# Lab5.net
KiCad netlist of a schematic drawn in EAGLE
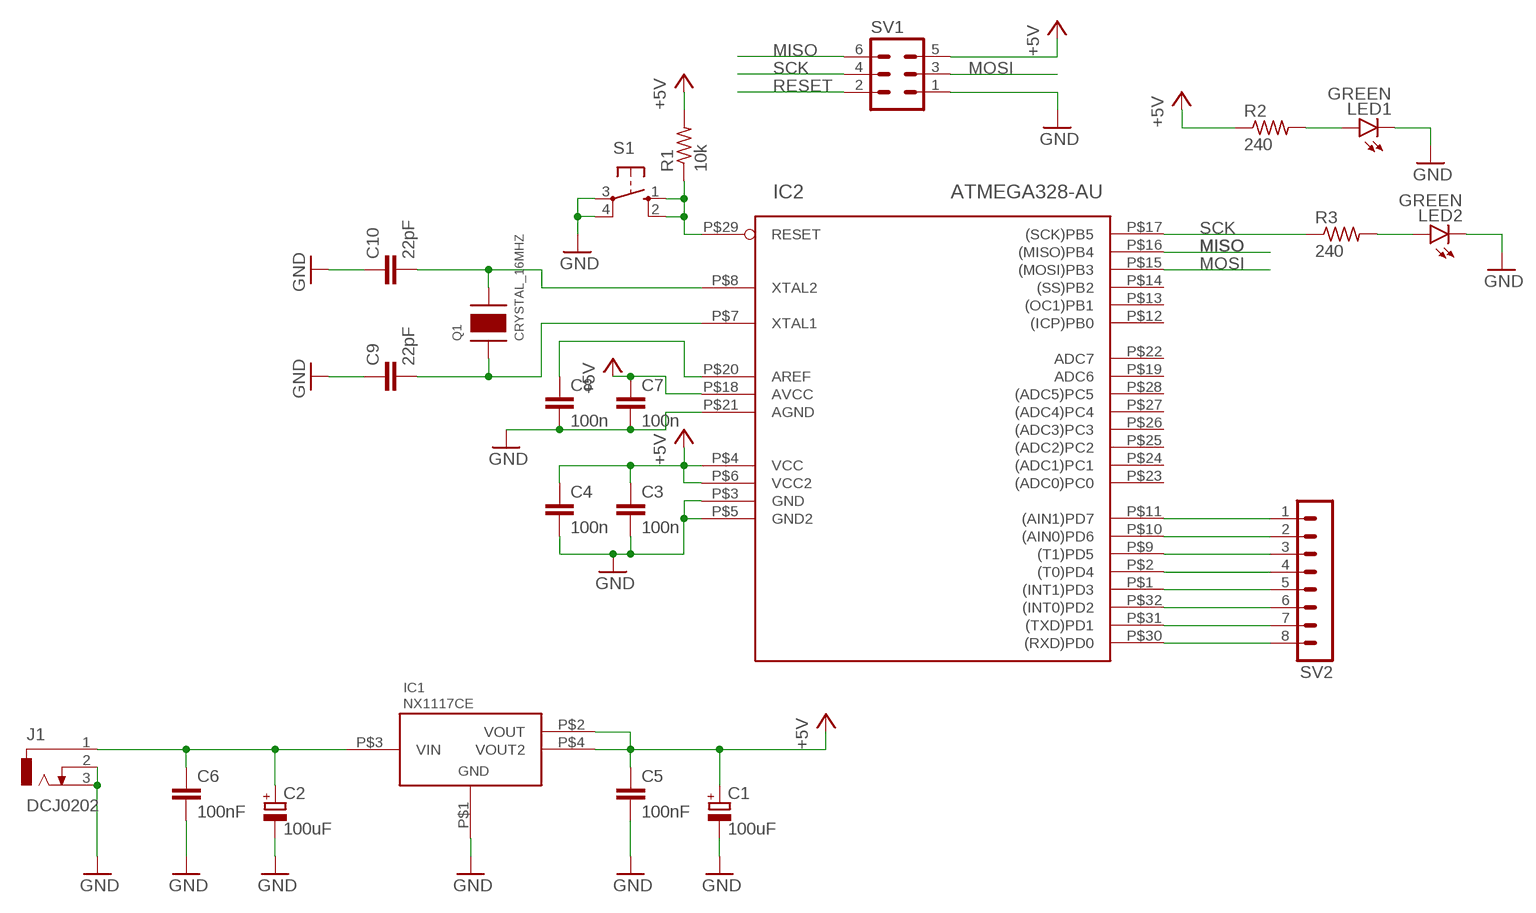
[diagram p0: schematic, sheet 1]

(export (version "E")
  (design (tool "Eeschema 10.0.6"))
  (components
    (comp (ref "C1")
      (value "100uF")
      (footprint "eagle-import:PANASONIC_D")
      (libsource (lib "eagle-import") (part "CPOL-EUD"))
    )
    (comp (ref "C2")
      (value "100uF")
      (footprint "eagle-import:PANASONIC_D")
      (libsource (lib "eagle-import") (part "CPOL-EUD"))
    )
    (comp (ref "C3")
      (value "100n")
      (footprint "eagle-import:C0603")
      (libsource (lib "eagle-import") (part "C-EUC0603"))
    )
    (comp (ref "C4")
      (value "100n")
      (footprint "eagle-import:C0603")
      (libsource (lib "eagle-import") (part "C-EUC0603"))
    )
    (comp (ref "C5")
      (value "100nF")
      (footprint "eagle-import:C0805")
      (libsource (lib "eagle-import") (part "C-EUC0805"))
    )
    (comp (ref "C6")
      (value "100nF")
      (footprint "eagle-import:C0805")
      (libsource (lib "eagle-import") (part "C-EUC0805"))
    )
    (comp (ref "C7")
      (value "100n")
      (footprint "eagle-import:C0603")
      (libsource (lib "eagle-import") (part "C-EUC0603"))
    )
    (comp (ref "C8")
      (value "100n")
      (footprint "eagle-import:C0603")
      (libsource (lib "eagle-import") (part "C-EUC0603"))
    )
    (comp (ref "C9")
      (value "22pF")
      (footprint "eagle-import:C0603")
      (libsource (lib "eagle-import") (part "C-EUC0603"))
    )
    (comp (ref "C10")
      (value "22pF")
      (footprint "eagle-import:C0603")
      (libsource (lib "eagle-import") (part "C-EUC0603"))
    )
    (comp (ref "IC1")
      (value "NX1117CE")
      (footprint "eagle-import:SOT223_NX")
      (libsource (lib "eagle-import") (part "NX1117CE"))
    )
    (comp (ref "IC2")
      (value "ATMEGA328-AU")
      (footprint "eagle-import:32-TQFP")
      (libsource (lib "eagle-import") (part "ATMEGA328-AU"))
    )
    (comp (ref "J1")
      (value "DCJ0202")
      (footprint "eagle-import:DCJ0202")
      (libsource (lib "eagle-import") (part "DCJ0202"))
    )
    (comp (ref "LED1")
      (value "GREEN")
      (footprint "eagle-import:CHIP-LED0603")
      (libsource (lib "eagle-import") (part "LEDCHIP-LED0603"))
    )
    (comp (ref "LED2")
      (value "GREEN")
      (footprint "eagle-import:CHIP-LED0603")
      (libsource (lib "eagle-import") (part "LEDCHIP-LED0603"))
    )
    (comp (ref "Q1")
      (value "CRYSTAL_16MHZ")
      (footprint "eagle-import:CRYSTAL_16MHZ")
      (libsource (lib "eagle-import") (part "CRYSTAL_16MHZ"))
    )
    (comp (ref "R1")
      (value "10k")
      (footprint "eagle-import:R0603")
      (libsource (lib "eagle-import") (part "R-US_R0603"))
    )
    (comp (ref "R2")
      (value "240")
      (footprint "eagle-import:R0603")
      (libsource (lib "eagle-import") (part "R-US_R0603"))
    )
    (comp (ref "R3")
      (value "240")
      (footprint "eagle-import:R0603")
      (libsource (lib "eagle-import") (part "R-US_R0603"))
    )
    (comp (ref "S1")
      (value "10-XX")
      (footprint "eagle-import:B3F-10XX")
      (fields (field (name "MPN") "B3F-1000"))
      (libsource (lib "eagle-import") (part "10-XX"))
    )
    (comp (ref "SV1")
      (value "MA03-2")
      (footprint "eagle-import:MA03-2")
      (libsource (lib "eagle-import") (part "MA03-2"))
    )
    (comp (ref "SV2")
      (value "MA08-1")
      (footprint "eagle-import:MA08-1")
      (libsource (lib "eagle-import") (part "MA08-1"))
    )
  )
  (nets
    (net (code "1") (name "+5V") (class "Default")
      (node (ref "C1") (pin "+") (pinfunction "+_+") (pintype "passive"))
      (node (ref "C3") (pin "1") (pinfunction "1_1") (pintype "passive"))
      (node (ref "C4") (pin "1") (pinfunction "1_1") (pintype "passive"))
      (node (ref "C5") (pin "1") (pinfunction "1_1") (pintype "passive"))
      (node (ref "C7") (pin "1") (pinfunction "1_1") (pintype "passive"))
      (node (ref "IC1") (pin "P$2") (pinfunction "VOUT_P$2") (pintype "bidirectional"))
      (node (ref "IC1") (pin "P$4") (pinfunction "VOUT2_P$4") (pintype "bidirectional"))
      (node (ref "IC2") (pin "P$18") (pinfunction "AVCC_P$18") (pintype "bidirectional"))
      (node (ref "IC2") (pin "P$4") (pinfunction "VCC_P$4") (pintype "bidirectional"))
      (node (ref "IC2") (pin "P$6") (pinfunction "VCC2_P$6") (pintype "bidirectional"))
      (node (ref "R1") (pin "2") (pinfunction "2_2") (pintype "passive"))
      (node (ref "R2") (pin "1") (pinfunction "1_1") (pintype "passive"))
      (node (ref "SV1") (pin "5") (pinfunction "5_5") (pintype "passive"))
    )
    (net (code "2") (name "/MISO") (class "Default")
      (node (ref "IC2") (pin "P$16") (pinfunction "(MISO)PB4_P$16") (pintype "bidirectional"))
      (node (ref "SV1") (pin "6") (pinfunction "6_6") (pintype "passive"))
    )
    (net (code "3") (name "/MOSI") (class "Default")
      (node (ref "IC2") (pin "P$15") (pinfunction "(MOSI)PB3_P$15") (pintype "bidirectional"))
      (node (ref "SV1") (pin "3") (pinfunction "3_3") (pintype "passive"))
    )
    (net (code "4") (name "/RESET") (class "Default")
      (node (ref "SV1") (pin "2") (pinfunction "2_2") (pintype "passive"))
    )
    (net (code "5") (name "/SCK") (class "Default")
      (node (ref "IC2") (pin "P$17") (pinfunction "(SCK)PB5_P$17") (pintype "bidirectional"))
      (node (ref "R3") (pin "1") (pinfunction "1_1") (pintype "passive"))
      (node (ref "SV1") (pin "4") (pinfunction "4_4") (pintype "passive"))
    )
    (net (code "6") (name "GND") (class "Default")
      (node (ref "C1") (pin "-") (pinfunction "-_-") (pintype "passive"))
      (node (ref "C10") (pin "1") (pinfunction "1_1") (pintype "passive"))
      (node (ref "C2") (pin "-") (pinfunction "-_-") (pintype "passive"))
      (node (ref "C3") (pin "2") (pinfunction "2_2") (pintype "passive"))
      (node (ref "C4") (pin "2") (pinfunction "2_2") (pintype "passive"))
      (node (ref "C5") (pin "2") (pinfunction "2_2") (pintype "passive"))
      (node (ref "C6") (pin "2") (pinfunction "2_2") (pintype "passive"))
      (node (ref "C7") (pin "2") (pinfunction "2_2") (pintype "passive"))
      (node (ref "C8") (pin "2") (pinfunction "2_2") (pintype "passive"))
      (node (ref "C9") (pin "1") (pinfunction "1_1") (pintype "passive"))
      (node (ref "IC1") (pin "P$1") (pinfunction "GND_P$1") (pintype "bidirectional"))
      (node (ref "IC2") (pin "P$21") (pinfunction "AGND_P$21") (pintype "bidirectional"))
      (node (ref "IC2") (pin "P$3") (pinfunction "GND_P$3") (pintype "bidirectional"))
      (node (ref "IC2") (pin "P$5") (pinfunction "GND2_P$5") (pintype "bidirectional"))
      (node (ref "J1") (pin "2") (pinfunction "2_2") (pintype "passive"))
      (node (ref "J1") (pin "3") (pinfunction "3_3") (pintype "passive"))
      (node (ref "LED1") (pin "C") (pinfunction "C_C") (pintype "passive"))
      (node (ref "LED2") (pin "C") (pinfunction "C_C") (pintype "passive"))
      (node (ref "S1") (pin "3") (pinfunction "P_3") (pintype "passive"))
      (node (ref "S1") (pin "4") (pinfunction "P1_4") (pintype "passive"))
      (node (ref "SV1") (pin "1") (pinfunction "1_1") (pintype "passive"))
    )
    (net (code "7") (name "Net-(IC1-VIN)") (class "Default")
      (node (ref "C2") (pin "+") (pinfunction "+_+") (pintype "passive"))
      (node (ref "C6") (pin "1") (pinfunction "1_1") (pintype "passive"))
      (node (ref "IC1") (pin "P$3") (pinfunction "VIN_P$3") (pintype "bidirectional"))
      (node (ref "J1") (pin "1") (pinfunction "1_1") (pintype "passive"))
    )
    (net (code "8") (name "Net-(IC2-(AIN0)PD6)") (class "Default")
      (node (ref "IC2") (pin "P$10") (pinfunction "(AIN0)PD6_P$10") (pintype "bidirectional"))
      (node (ref "SV2") (pin "2") (pinfunction "2_2") (pintype "passive"))
    )
    (net (code "9") (name "Net-(IC2-(AIN1)PD7)") (class "Default")
      (node (ref "IC2") (pin "P$11") (pinfunction "(AIN1)PD7_P$11") (pintype "bidirectional"))
      (node (ref "SV2") (pin "1") (pinfunction "1_1") (pintype "passive"))
    )
    (net (code "10") (name "Net-(IC2-(INT0)PD2)") (class "Default")
      (node (ref "IC2") (pin "P$32") (pinfunction "(INT0)PD2_P$32") (pintype "bidirectional"))
      (node (ref "SV2") (pin "6") (pinfunction "6_6") (pintype "passive"))
    )
    (net (code "11") (name "Net-(IC2-(INT1)PD3)") (class "Default")
      (node (ref "IC2") (pin "P$1") (pinfunction "(INT1)PD3_P$1") (pintype "bidirectional"))
      (node (ref "SV2") (pin "5") (pinfunction "5_5") (pintype "passive"))
    )
    (net (code "12") (name "Net-(IC2-(RXD)PD0)") (class "Default")
      (node (ref "IC2") (pin "P$30") (pinfunction "(RXD)PD0_P$30") (pintype "bidirectional"))
      (node (ref "SV2") (pin "8") (pinfunction "8_8") (pintype "passive"))
    )
    (net (code "13") (name "Net-(IC2-(T0)PD4)") (class "Default")
      (node (ref "IC2") (pin "P$2") (pinfunction "(T0)PD4_P$2") (pintype "bidirectional"))
      (node (ref "SV2") (pin "4") (pinfunction "4_4") (pintype "passive"))
    )
    (net (code "14") (name "Net-(IC2-(T1)PD5)") (class "Default")
      (node (ref "IC2") (pin "P$9") (pinfunction "(T1)PD5_P$9") (pintype "bidirectional"))
      (node (ref "SV2") (pin "3") (pinfunction "3_3") (pintype "passive"))
    )
    (net (code "15") (name "Net-(IC2-(TXD)PD1)") (class "Default")
      (node (ref "IC2") (pin "P$31") (pinfunction "(TXD)PD1_P$31") (pintype "bidirectional"))
      (node (ref "SV2") (pin "7") (pinfunction "7_7") (pintype "passive"))
    )
    (net (code "16") (name "Net-(IC2-AREF)") (class "Default")
      (node (ref "C8") (pin "1") (pinfunction "1_1") (pintype "passive"))
      (node (ref "IC2") (pin "P$20") (pinfunction "AREF_P$20") (pintype "bidirectional"))
    )
    (net (code "17") (name "Net-(IC2-RESET)") (class "Default")
      (node (ref "IC2") (pin "P$29") (pinfunction "RESET_P$29") (pintype "bidirectional"))
      (node (ref "R1") (pin "1") (pinfunction "1_1") (pintype "passive"))
      (node (ref "S1") (pin "1") (pinfunction "S_1") (pintype "passive"))
      (node (ref "S1") (pin "2") (pinfunction "S1_2") (pintype "passive"))
    )
    (net (code "18") (name "Net-(IC2-XTAL1)") (class "Default")
      (node (ref "C9") (pin "2") (pinfunction "2_2") (pintype "passive"))
      (node (ref "IC2") (pin "P$7") (pinfunction "XTAL1_P$7") (pintype "bidirectional"))
      (node (ref "Q1") (pin "P$1") (pinfunction "P$1_P$1") (pintype "bidirectional"))
    )
    (net (code "19") (name "Net-(IC2-XTAL2)") (class "Default")
      (node (ref "C10") (pin "2") (pinfunction "2_2") (pintype "passive"))
      (node (ref "IC2") (pin "P$8") (pinfunction "XTAL2_P$8") (pintype "bidirectional"))
      (node (ref "Q1") (pin "P$2") (pinfunction "P$2_P$2") (pintype "bidirectional"))
    )
    (net (code "20") (name "Net-(LED1-PadA)") (class "Default")
      (node (ref "LED1") (pin "A") (pinfunction "A_A") (pintype "passive"))
      (node (ref "R2") (pin "2") (pinfunction "2_2") (pintype "passive"))
    )
    (net (code "21") (name "Net-(LED2-PadA)") (class "Default")
      (node (ref "LED2") (pin "A") (pinfunction "A_A") (pintype "passive"))
      (node (ref "R3") (pin "2") (pinfunction "2_2") (pintype "passive"))
    )
    (net (code "22") (name "unconnected-(IC2-(ADC0)PC0-PadP$23)") (class "Default")
      (node (ref "IC2") (pin "P$23") (pinfunction "(ADC0)PC0_P$23") (pintype "bidirectional"))
    )
    (net (code "23") (name "unconnected-(IC2-(ADC1)PC1-PadP$24)") (class "Default")
      (node (ref "IC2") (pin "P$24") (pinfunction "(ADC1)PC1_P$24") (pintype "bidirectional"))
    )
    (net (code "24") (name "unconnected-(IC2-(ADC2)PC2-PadP$25)") (class "Default")
      (node (ref "IC2") (pin "P$25") (pinfunction "(ADC2)PC2_P$25") (pintype "bidirectional"))
    )
    (net (code "25") (name "unconnected-(IC2-(ADC3)PC3-PadP$26)") (class "Default")
      (node (ref "IC2") (pin "P$26") (pinfunction "(ADC3)PC3_P$26") (pintype "bidirectional"))
    )
    (net (code "26") (name "unconnected-(IC2-(ADC4)PC4-PadP$27)") (class "Default")
      (node (ref "IC2") (pin "P$27") (pinfunction "(ADC4)PC4_P$27") (pintype "bidirectional"))
    )
    (net (code "27") (name "unconnected-(IC2-(ADC5)PC5-PadP$28)") (class "Default")
      (node (ref "IC2") (pin "P$28") (pinfunction "(ADC5)PC5_P$28") (pintype "bidirectional"))
    )
    (net (code "28") (name "unconnected-(IC2-(ICP)PB0-PadP$12)") (class "Default")
      (node (ref "IC2") (pin "P$12") (pinfunction "(ICP)PB0_P$12") (pintype "bidirectional"))
    )
    (net (code "29") (name "unconnected-(IC2-(OC1)PB1-PadP$13)") (class "Default")
      (node (ref "IC2") (pin "P$13") (pinfunction "(OC1)PB1_P$13") (pintype "bidirectional"))
    )
    (net (code "30") (name "unconnected-(IC2-(SS)PB2-PadP$14)") (class "Default")
      (node (ref "IC2") (pin "P$14") (pinfunction "(SS)PB2_P$14") (pintype "bidirectional"))
    )
    (net (code "31") (name "unconnected-(IC2-ADC6-PadP$19)") (class "Default")
      (node (ref "IC2") (pin "P$19") (pinfunction "ADC6_P$19") (pintype "bidirectional"))
    )
    (net (code "32") (name "unconnected-(IC2-ADC7-PadP$22)") (class "Default")
      (node (ref "IC2") (pin "P$22") (pinfunction "ADC7_P$22") (pintype "bidirectional"))
    )
  )
)
